# smoothieboard-alt-p4.net
KiCad netlist of a schematic drawn in Altium Designer
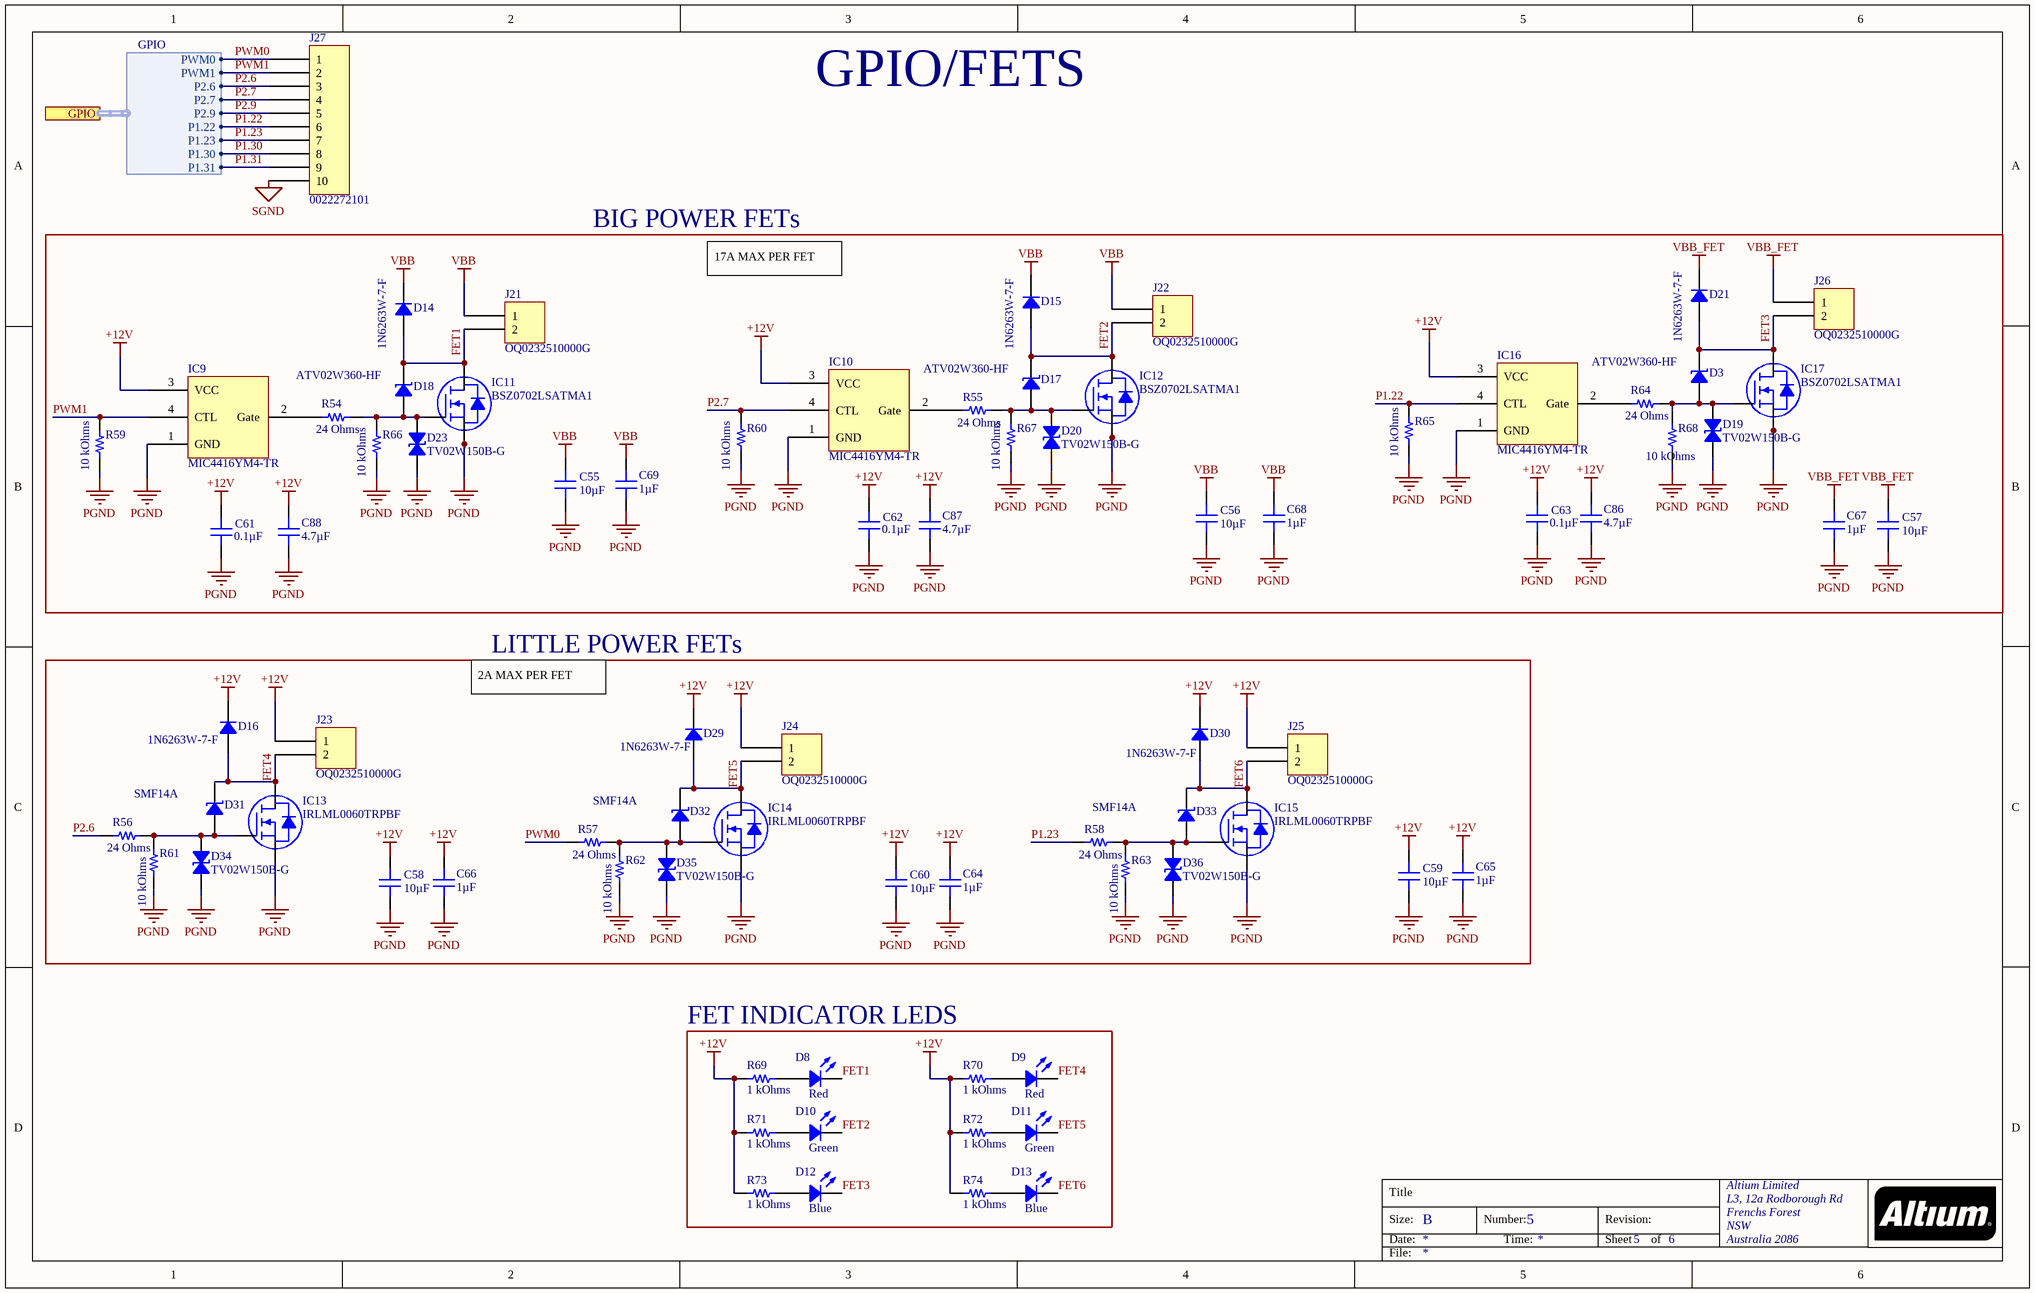
[diagram p0: smoothieboard-alt-p4.SchDoc]

(export (version "E")
  (design (tool "Eeschema 10.0.6"))
  (components
    (comp (ref "C55")
      (value "10µF")
      (footprint "CAP 0603_1608")
      (description "CAP CER 10UF 6.3V X5R 0603")
      (fields
        (field (name "PART NUMBER") "GRM188R60J106KE47D")
        (field (name "MANUFACTURER") "Murata Electronics")
      )
      (libsource (lib "CAL") (part "Capacitor"))
    )
    (comp (ref "C56")
      (value "10µF")
      (footprint "CAP 0603_1608")
      (description "CAP CER 10UF 6.3V X5R 0603")
      (fields
        (field (name "PART NUMBER") "GRM188R60J106KE47D")
        (field (name "MANUFACTURER") "Murata Electronics")
      )
      (libsource (lib "CAL") (part "Capacitor"))
    )
    (comp (ref "C57")
      (value "10µF")
      (footprint "CAP 0603_1608")
      (description "CAP CER 10UF 6.3V X5R 0603")
      (fields
        (field (name "PART NUMBER") "GRM188R60J106KE47D")
        (field (name "MANUFACTURER") "Murata Electronics")
      )
      (libsource (lib "CAL") (part "Capacitor"))
    )
    (comp (ref "C58")
      (value "10µF")
      (footprint "CAP 0603_1608")
      (description "CAP CER 10UF 6.3V X5R 0603")
      (fields
        (field (name "PART NUMBER") "GRM188R60J106KE47D")
        (field (name "MANUFACTURER") "Murata Electronics")
      )
      (libsource (lib "CAL") (part "Capacitor"))
    )
    (comp (ref "C59")
      (value "10µF")
      (footprint "CAP 0603_1608")
      (description "CAP CER 10UF 6.3V X5R 0603")
      (fields
        (field (name "PART NUMBER") "GRM188R60J106KE47D")
        (field (name "MANUFACTURER") "Murata Electronics")
      )
      (libsource (lib "CAL") (part "Capacitor"))
    )
    (comp (ref "C60")
      (value "10µF")
      (footprint "CAP 0603_1608")
      (description "CAP CER 10UF 6.3V X5R 0603")
      (fields
        (field (name "PART NUMBER") "GRM188R60J106KE47D")
        (field (name "MANUFACTURER") "Murata Electronics")
      )
      (libsource (lib "CAL") (part "Capacitor"))
    )
    (comp (ref "C61")
      (value "0.1µF")
      (footprint "CAP 0603_1608")
      (description "CAP CER 0.1UF 50V X7R 0603")
      (fields
        (field (name "PART NUMBER") "CML0603X7R104KT50V")
        (field (name "MANUFACTURER") "Stackpole Electronics Inc")
      )
      (libsource (lib "CAL") (part "Capacitor"))
    )
    (comp (ref "C62")
      (value "0.1µF")
      (footprint "CAP 0603_1608")
      (description "CAP CER 0.1UF 50V X7R 0603")
      (fields
        (field (name "PART NUMBER") "CML0603X7R104KT50V")
        (field (name "MANUFACTURER") "Stackpole Electronics Inc")
      )
      (libsource (lib "CAL") (part "Capacitor"))
    )
    (comp (ref "C63")
      (value "0.1µF")
      (footprint "CAP 0603_1608")
      (description "CAP CER 0.1UF 50V X7R 0603")
      (fields
        (field (name "PART NUMBER") "CML0603X7R104KT50V")
        (field (name "MANUFACTURER") "Stackpole Electronics Inc")
      )
      (libsource (lib "CAL") (part "Capacitor"))
    )
    (comp (ref "C64")
      (value "1µF")
      (footprint "CAP 0805_2012")
      (description "CAP CER 1UF 100V X7R 0805")
      (fields (field (name "PART NUMBER") "08051C105K4Z2A") (field (name "MANUFACTURER") "AVX Corporation"))
      (libsource (lib "CAL") (part "Capacitor"))
    )
    (comp (ref "C65")
      (value "1µF")
      (footprint "CAP 0805_2012")
      (description "CAP CER 1UF 100V X7R 0805")
      (fields (field (name "PART NUMBER") "08051C105K4Z2A") (field (name "MANUFACTURER") "AVX Corporation"))
      (libsource (lib "CAL") (part "Capacitor"))
    )
    (comp (ref "C66")
      (value "1µF")
      (footprint "CAP 0805_2012")
      (description "CAP CER 1UF 100V X7R 0805")
      (fields (field (name "PART NUMBER") "08051C105K4Z2A") (field (name "MANUFACTURER") "AVX Corporation"))
      (libsource (lib "CAL") (part "Capacitor"))
    )
    (comp (ref "C67")
      (value "1µF")
      (footprint "CAP 0805_2012")
      (description "CAP CER 1UF 100V X7R 0805")
      (fields (field (name "PART NUMBER") "08051C105K4Z2A") (field (name "MANUFACTURER") "AVX Corporation"))
      (libsource (lib "CAL") (part "Capacitor"))
    )
    (comp (ref "C68")
      (value "1µF")
      (footprint "CAP 0805_2012")
      (description "CAP CER 1UF 100V X7R 0805")
      (fields (field (name "PART NUMBER") "08051C105K4Z2A") (field (name "MANUFACTURER") "AVX Corporation"))
      (libsource (lib "CAL") (part "Capacitor"))
    )
    (comp (ref "C69")
      (value "1µF")
      (footprint "CAP 0805_2012")
      (description "CAP CER 1UF 100V X7R 0805")
      (fields (field (name "PART NUMBER") "08051C105K4Z2A") (field (name "MANUFACTURER") "AVX Corporation"))
      (libsource (lib "CAL") (part "Capacitor"))
    )
    (comp (ref "C86")
      (value "4.7µF")
      (footprint "CAP 0603_1608")
      (description "CAP CER 4.7UF 16V X5R 0603")
      (fields
        (field (name "PART NUMBER") "C1608X5R1C475K080AE")
        (field (name "MANUFACTURER") "TDK Corporation")
      )
      (libsource (lib "CAL") (part "Capacitor"))
    )
    (comp (ref "C87")
      (value "4.7µF")
      (footprint "CAP 0603_1608")
      (description "CAP CER 4.7UF 16V X5R 0603")
      (fields
        (field (name "PART NUMBER") "C1608X5R1C475K080AE")
        (field (name "MANUFACTURER") "TDK Corporation")
      )
      (libsource (lib "CAL") (part "Capacitor"))
    )
    (comp (ref "C88")
      (value "4.7µF")
      (footprint "CAP 0603_1608")
      (description "CAP CER 4.7UF 16V X5R 0603")
      (fields
        (field (name "PART NUMBER") "C1608X5R1C475K080AE")
        (field (name "MANUFACTURER") "TDK Corporation")
      )
      (libsource (lib "CAL") (part "Capacitor"))
    )
    (comp (ref "D3")
      (value "ATV02W360-HF")
      (footprint "SOD123F")
      (description "TVS DIODE 36V 58.1V SOD123")
      (fields (field (name "MANUFACTURER") "Comchip Technology"))
      (libsource (lib "CAL") (part "DIODE TVS UNI"))
    )
    (comp (ref "D8")
      (value "Red")
      (footprint "LED 0805_2012 RED")
      (description "LED RED CLEAR SMD")
      (fields (field (name "PART NUMBER") "LTST-C171KRKT") (field (name "MANUFACTURER") "Lite-On Inc."))
      (libsource (lib "CAL") (part "LED"))
    )
    (comp (ref "D9")
      (value "Red")
      (footprint "LED 0805_2012 RED")
      (description "LED RED CLEAR SMD")
      (fields (field (name "PART NUMBER") "LTST-C171KRKT") (field (name "MANUFACTURER") "Lite-On Inc."))
      (libsource (lib "CAL") (part "LED"))
    )
    (comp (ref "D10")
      (value "Green")
      (footprint "LED 0805_2012 GREEN")
      (description "LED GREEN CLEAR SMD")
      (fields (field (name "PART NUMBER") "LTST-C171KGKT") (field (name "MANUFACTURER") "Lite-On Inc."))
      (libsource (lib "CAL") (part "LED"))
    )
    (comp (ref "D11")
      (value "Green")
      (footprint "LED 0805_2012 GREEN")
      (description "LED GREEN CLEAR SMD")
      (fields (field (name "PART NUMBER") "LTST-C171KGKT") (field (name "MANUFACTURER") "Lite-On Inc."))
      (libsource (lib "CAL") (part "LED"))
    )
    (comp (ref "D12")
      (value "Blue")
      (footprint "LED 0805_2012 BLUE")
      (description "LED BLUE CLEAR SMD")
      (fields (field (name "PART NUMBER") "LTST-C170TBKT") (field (name "MANUFACTURER") "Lite-On Inc."))
      (libsource (lib "CAL") (part "LED"))
    )
    (comp (ref "D13")
      (value "Blue")
      (footprint "LED 0805_2012 BLUE")
      (description "LED BLUE CLEAR SMD")
      (fields (field (name "PART NUMBER") "LTST-C170TBKT") (field (name "MANUFACTURER") "Lite-On Inc."))
      (libsource (lib "CAL") (part "LED"))
    )
    (comp (ref "D14")
      (value "1N6263W-7-F")
      (footprint "SOD-123")
      (description "DIODE SCHOTTKY 60V 15MA SOD123")
      (fields (field (name "MANUFACTURER") "Diodes Incorporated"))
      (libsource (lib "CAL") (part "Diode"))
    )
    (comp (ref "D15")
      (value "1N6263W-7-F")
      (footprint "SOD-123")
      (description "DIODE SCHOTTKY 60V 15MA SOD123")
      (fields (field (name "MANUFACTURER") "Diodes Incorporated"))
      (libsource (lib "CAL") (part "Diode"))
    )
    (comp (ref "D16")
      (value "1N6263W-7-F")
      (footprint "SOD-123")
      (description "DIODE SCHOTTKY 60V 15MA SOD123")
      (fields (field (name "MANUFACTURER") "Diodes Incorporated"))
      (libsource (lib "CAL") (part "Diode"))
    )
    (comp (ref "D17")
      (value "ATV02W360-HF")
      (footprint "SOD123F")
      (description "TVS DIODE 36V 58.1V SOD123")
      (fields (field (name "MANUFACTURER") "Comchip Technology"))
      (libsource (lib "CAL") (part "DIODE TVS UNI"))
    )
    (comp (ref "D18")
      (value "ATV02W360-HF")
      (footprint "SOD123F")
      (description "TVS DIODE 36V 58.1V SOD123")
      (fields (field (name "MANUFACTURER") "Comchip Technology"))
      (libsource (lib "CAL") (part "DIODE TVS UNI"))
    )
    (comp (ref "D19")
      (value "TV02W150B-G")
      (footprint "SOD-123")
      (description "TVS DIODE 15V 24.4V SOD123")
      (fields (field (name "MANUFACTURER") "Comchip Technology"))
      (libsource (lib "CAL") (part "Diode TVS"))
    )
    (comp (ref "D20")
      (value "TV02W150B-G")
      (footprint "SOD-123")
      (description "TVS DIODE 15V 24.4V SOD123")
      (fields (field (name "MANUFACTURER") "Comchip Technology"))
      (libsource (lib "CAL") (part "Diode TVS"))
    )
    (comp (ref "D21")
      (value "1N6263W-7-F")
      (footprint "SOD-123")
      (description "DIODE SCHOTTKY 60V 15MA SOD123")
      (fields (field (name "MANUFACTURER") "Diodes Incorporated"))
      (libsource (lib "CAL") (part "Diode"))
    )
    (comp (ref "D23")
      (value "TV02W150B-G")
      (footprint "SOD-123")
      (description "TVS DIODE 15V 24.4V SOD123")
      (fields (field (name "MANUFACTURER") "Comchip Technology"))
      (libsource (lib "CAL") (part "Diode TVS"))
    )
    (comp (ref "D29")
      (value "1N6263W-7-F")
      (footprint "SOD-123")
      (description "DIODE SCHOTTKY 60V 15MA SOD123")
      (fields (field (name "MANUFACTURER") "Diodes Incorporated"))
      (libsource (lib "CAL") (part "Diode"))
    )
    (comp (ref "D30")
      (value "1N6263W-7-F")
      (footprint "SOD-123")
      (description "DIODE SCHOTTKY 60V 15MA SOD123")
      (fields (field (name "MANUFACTURER") "Diodes Incorporated"))
      (libsource (lib "CAL") (part "Diode"))
    )
    (comp (ref "D31")
      (value "SMF14A")
      (footprint "SOD123F")
      (description "TVS DIODE 14V 23.2V SOD123F")
      (fields (field (name "MANUFACTURER") "Littelfuse Inc."))
      (libsource (lib "CAL") (part "DIODE TVS UNI"))
    )
    (comp (ref "D32")
      (value "SMF14A")
      (footprint "SOD123F")
      (description "TVS DIODE 14V 23.2V SOD123F")
      (fields (field (name "MANUFACTURER") "Littelfuse Inc."))
      (libsource (lib "CAL") (part "DIODE TVS UNI"))
    )
    (comp (ref "D33")
      (value "SMF14A")
      (footprint "SOD123F")
      (description "TVS DIODE 14V 23.2V SOD123F")
      (fields (field (name "MANUFACTURER") "Littelfuse Inc."))
      (libsource (lib "CAL") (part "DIODE TVS UNI"))
    )
    (comp (ref "D34")
      (value "TV02W150B-G")
      (footprint "SOD-123")
      (description "TVS DIODE 15V 24.4V SOD123")
      (fields (field (name "MANUFACTURER") "Comchip Technology"))
      (libsource (lib "CAL") (part "Diode TVS"))
    )
    (comp (ref "D35")
      (value "TV02W150B-G")
      (footprint "SOD-123")
      (description "TVS DIODE 15V 24.4V SOD123")
      (fields (field (name "MANUFACTURER") "Comchip Technology"))
      (libsource (lib "CAL") (part "Diode TVS"))
    )
    (comp (ref "D36")
      (value "TV02W150B-G")
      (footprint "SOD-123")
      (description "TVS DIODE 15V 24.4V SOD123")
      (fields (field (name "MANUFACTURER") "Comchip Technology"))
      (libsource (lib "CAL") (part "Diode TVS"))
    )
    (comp (ref "IC9")
      (value "MIC4416YM4-TR")
      (footprint "MICROCHIP SOT-143-4")
      (description "IC GATE DRVR LOW-SIDE SOT143")
      (fields (field (name "MANUFACTURER") "Microchip Technology"))
      (libsource (lib "CAL") (part "MICROCHIP MIC4416"))
    )
    (comp (ref "IC10")
      (value "MIC4416YM4-TR")
      (footprint "MICROCHIP SOT-143-4")
      (description "IC GATE DRVR LOW-SIDE SOT143")
      (fields (field (name "MANUFACTURER") "Microchip Technology"))
      (libsource (lib "CAL") (part "MICROCHIP MIC4416"))
    )
    (comp (ref "IC11")
      (value "BSZ0702LSATMA1")
      (footprint "INFINEON PG-TSDSON-8")
      (description "TRENCH 40<-<100V")
      (fields (field (name "MANUFACTURER") "Infineon Technologies"))
      (libsource (lib "CAL") (part "INFINEON BSZ MOSFET N-CH"))
    )
    (comp (ref "IC12")
      (value "BSZ0702LSATMA1")
      (footprint "INFINEON PG-TSDSON-8")
      (description "TRENCH 40<-<100V")
      (fields (field (name "MANUFACTURER") "Infineon Technologies"))
      (libsource (lib "CAL") (part "INFINEON BSZ MOSFET N-CH"))
    )
    (comp (ref "IC13")
      (value "IRLML0060TRPBF")
      (footprint "INFINEON SOT-23-3")
      (description "MOSFET N-CH 60V 2.7A SOT-23-3")
      (fields (field (name "MANUFACTURER") "Infineon Technologies"))
      (libsource (lib "CAL") (part "INFINEON MOSFET N-CH SOT-23-3 GSD"))
    )
    (comp (ref "IC14")
      (value "IRLML0060TRPBF")
      (footprint "INFINEON SOT-23-3")
      (description "MOSFET N-CH 60V 2.7A SOT-23-3")
      (fields (field (name "MANUFACTURER") "Infineon Technologies"))
      (libsource (lib "CAL") (part "INFINEON MOSFET N-CH SOT-23-3 GSD"))
    )
    (comp (ref "IC15")
      (value "IRLML0060TRPBF")
      (footprint "INFINEON SOT-23-3")
      (description "MOSFET N-CH 60V 2.7A SOT-23-3")
      (fields (field (name "MANUFACTURER") "Infineon Technologies"))
      (libsource (lib "CAL") (part "INFINEON MOSFET N-CH SOT-23-3 GSD"))
    )
    (comp (ref "IC16")
      (value "MIC4416YM4-TR")
      (footprint "MICROCHIP SOT-143-4")
      (description "IC GATE DRVR LOW-SIDE SOT143")
      (fields (field (name "MANUFACTURER") "Microchip Technology"))
      (libsource (lib "CAL") (part "MICROCHIP MIC4416"))
    )
    (comp (ref "IC17")
      (value "BSZ0702LSATMA1")
      (footprint "INFINEON PG-TSDSON-8")
      (description "TRENCH 40<-<100V")
      (fields (field (name "MANUFACTURER") "Infineon Technologies"))
      (libsource (lib "CAL") (part "INFINEON BSZ MOSFET N-CH"))
    )
    (comp (ref "J21")
      (value "OQ0232510000G")
      (footprint "FCI 06-381-2PIN")
      (description "TERM BLOCK HDR 2POS 90DEG 3.81MM")
      (fields (field (name "MANUFACTURER") "Amphenol Anytek"))
      (libsource (lib "CAL") (part "2 Pin"))
    )
    (comp (ref "J22")
      (value "OQ0232510000G")
      (footprint "FCI 06-381-2PIN")
      (description "TERM BLOCK HDR 2POS 90DEG 3.81MM")
      (fields (field (name "MANUFACTURER") "Amphenol Anytek"))
      (libsource (lib "CAL") (part "2 Pin"))
    )
    (comp (ref "J23")
      (value "OQ0232510000G")
      (footprint "FCI 06-381-2PIN")
      (description "TERM BLOCK HDR 2POS 90DEG 3.81MM")
      (fields (field (name "MANUFACTURER") "Amphenol Anytek"))
      (libsource (lib "CAL") (part "2 Pin"))
    )
    (comp (ref "J24")
      (value "OQ0232510000G")
      (footprint "FCI 06-381-2PIN")
      (description "TERM BLOCK HDR 2POS 90DEG 3.81MM")
      (fields (field (name "MANUFACTURER") "Amphenol Anytek"))
      (libsource (lib "CAL") (part "2 Pin"))
    )
    (comp (ref "J25")
      (value "OQ0232510000G")
      (footprint "FCI 06-381-2PIN")
      (description "TERM BLOCK HDR 2POS 90DEG 3.81MM")
      (fields (field (name "MANUFACTURER") "Amphenol Anytek"))
      (libsource (lib "CAL") (part "2 Pin"))
    )
    (comp (ref "J26")
      (value "OQ0232510000G")
      (footprint "FCI 06-381-2PIN")
      (description "TERM BLOCK HDR 2POS 90DEG 3.81MM")
      (fields (field (name "MANUFACTURER") "Amphenol Anytek"))
      (libsource (lib "CAL") (part "2 Pin"))
    )
    (comp (ref "J27")
      (value "0022272101")
      (footprint "MOLEX KK 0022272101")
      (description "CONN HEADER VERT 10POS 2.54MM")
      (fields (field (name "MANUFACTURER") "Molex"))
      (libsource (lib "CAL") (part "10 Pin"))
    )
    (comp (ref "R54")
      (value "24 Ohms")
      (footprint "RES 0402_1005")
      (description "RES SMD 24 OHM 1% 1/5W 0402")
      (fields
        (field (name "PART NUMBER") "ERJ-PA2F24R0X")
        (field (name "MANUFACTURER") "Panasonic Electronic Components")
      )
      (libsource (lib "CAL") (part "Resistor"))
    )
    (comp (ref "R55")
      (value "24 Ohms")
      (footprint "RES 0402_1005")
      (description "RES SMD 24 OHM 1% 1/5W 0402")
      (fields
        (field (name "PART NUMBER") "ERJ-PA2F24R0X")
        (field (name "MANUFACTURER") "Panasonic Electronic Components")
      )
      (libsource (lib "CAL") (part "Resistor"))
    )
    (comp (ref "R56")
      (value "24 Ohms")
      (footprint "RES 0402_1005")
      (description "RES SMD 24 OHM 1% 1/5W 0402")
      (fields
        (field (name "PART NUMBER") "ERJ-PA2F24R0X")
        (field (name "MANUFACTURER") "Panasonic Electronic Components")
      )
      (libsource (lib "CAL") (part "Resistor"))
    )
    (comp (ref "R57")
      (value "24 Ohms")
      (footprint "RES 0402_1005")
      (description "RES SMD 24 OHM 1% 1/5W 0402")
      (fields
        (field (name "PART NUMBER") "ERJ-PA2F24R0X")
        (field (name "MANUFACTURER") "Panasonic Electronic Components")
      )
      (libsource (lib "CAL") (part "Resistor"))
    )
    (comp (ref "R58")
      (value "24 Ohms")
      (footprint "RES 0402_1005")
      (description "RES SMD 24 OHM 1% 1/5W 0402")
      (fields
        (field (name "PART NUMBER") "ERJ-PA2F24R0X")
        (field (name "MANUFACTURER") "Panasonic Electronic Components")
      )
      (libsource (lib "CAL") (part "Resistor"))
    )
    (comp (ref "R59")
      (value "10 kOhms")
      (footprint "RES 0402_1005")
      (description "RES SMD 10K OHM 5% 1/16W 0402")
      (fields (field (name "PART NUMBER") "CRCW040210K0JNTD") (field (name "MANUFACTURER") "Vishay Dale"))
      (libsource (lib "CAL") (part "Resistor"))
    )
    (comp (ref "R60")
      (value "10 kOhms")
      (footprint "RES 0402_1005")
      (description "RES SMD 10K OHM 5% 1/16W 0402")
      (fields (field (name "PART NUMBER") "CRCW040210K0JNTD") (field (name "MANUFACTURER") "Vishay Dale"))
      (libsource (lib "CAL") (part "Resistor"))
    )
    (comp (ref "R61")
      (value "10 kOhms")
      (footprint "RES 0402_1005")
      (description "RES SMD 10K OHM 5% 1/16W 0402")
      (fields (field (name "PART NUMBER") "CRCW040210K0JNTD") (field (name "MANUFACTURER") "Vishay Dale"))
      (libsource (lib "CAL") (part "Resistor"))
    )
    (comp (ref "R62")
      (value "10 kOhms")
      (footprint "RES 0402_1005")
      (description "RES SMD 10K OHM 5% 1/16W 0402")
      (fields (field (name "PART NUMBER") "CRCW040210K0JNTD") (field (name "MANUFACTURER") "Vishay Dale"))
      (libsource (lib "CAL") (part "Resistor"))
    )
    (comp (ref "R63")
      (value "10 kOhms")
      (footprint "RES 0402_1005")
      (description "RES SMD 10K OHM 5% 1/16W 0402")
      (fields (field (name "PART NUMBER") "CRCW040210K0JNTD") (field (name "MANUFACTURER") "Vishay Dale"))
      (libsource (lib "CAL") (part "Resistor"))
    )
    (comp (ref "R64")
      (value "24 Ohms")
      (footprint "RES 0402_1005")
      (description "RES SMD 24 OHM 1% 1/5W 0402")
      (fields
        (field (name "PART NUMBER") "ERJ-PA2F24R0X")
        (field (name "MANUFACTURER") "Panasonic Electronic Components")
      )
      (libsource (lib "CAL") (part "Resistor"))
    )
    (comp (ref "R65")
      (value "10 kOhms")
      (footprint "RES 0402_1005")
      (description "RES SMD 10K OHM 5% 1/16W 0402")
      (fields (field (name "PART NUMBER") "CRCW040210K0JNTD") (field (name "MANUFACTURER") "Vishay Dale"))
      (libsource (lib "CAL") (part "Resistor"))
    )
    (comp (ref "R66")
      (value "10 kOhms")
      (footprint "RES 0402_1005")
      (description "RES SMD 10K OHM 5% 1/16W 0402")
      (fields (field (name "PART NUMBER") "CRCW040210K0JNTD") (field (name "MANUFACTURER") "Vishay Dale"))
      (libsource (lib "CAL") (part "Resistor"))
    )
    (comp (ref "R67")
      (value "10 kOhms")
      (footprint "RES 0402_1005")
      (description "RES SMD 10K OHM 5% 1/16W 0402")
      (fields (field (name "PART NUMBER") "CRCW040210K0JNTD") (field (name "MANUFACTURER") "Vishay Dale"))
      (libsource (lib "CAL") (part "Resistor"))
    )
    (comp (ref "R68")
      (value "10 kOhms")
      (footprint "RES 0402_1005")
      (description "RES SMD 10K OHM 5% 1/16W 0402")
      (fields (field (name "PART NUMBER") "CRCW040210K0JNTD") (field (name "MANUFACTURER") "Vishay Dale"))
      (libsource (lib "CAL") (part "Resistor"))
    )
    (comp (ref "R69")
      (value "1 kOhms")
      (footprint "RES 0402_1005")
      (description "RES SMD 1K OHM 1% 1/5W 0402")
      (fields (field (name "PART NUMBER") "CRCW04021K00FKEDHP") (field (name "MANUFACTURER") "Vishay Dale"))
      (libsource (lib "CAL") (part "Resistor"))
    )
    (comp (ref "R70")
      (value "1 kOhms")
      (footprint "RES 0402_1005")
      (description "RES SMD 1K OHM 1% 1/5W 0402")
      (fields (field (name "PART NUMBER") "CRCW04021K00FKEDHP") (field (name "MANUFACTURER") "Vishay Dale"))
      (libsource (lib "CAL") (part "Resistor"))
    )
    (comp (ref "R71")
      (value "1 kOhms")
      (footprint "RES 0402_1005")
      (description "RES SMD 1K OHM 1% 1/5W 0402")
      (fields (field (name "PART NUMBER") "CRCW04021K00FKEDHP") (field (name "MANUFACTURER") "Vishay Dale"))
      (libsource (lib "CAL") (part "Resistor"))
    )
    (comp (ref "R72")
      (value "1 kOhms")
      (footprint "RES 0402_1005")
      (description "RES SMD 1K OHM 1% 1/5W 0402")
      (fields (field (name "PART NUMBER") "CRCW04021K00FKEDHP") (field (name "MANUFACTURER") "Vishay Dale"))
      (libsource (lib "CAL") (part "Resistor"))
    )
    (comp (ref "R73")
      (value "1 kOhms")
      (footprint "RES 0402_1005")
      (description "RES SMD 1K OHM 1% 1/5W 0402")
      (fields (field (name "PART NUMBER") "CRCW04021K00FKEDHP") (field (name "MANUFACTURER") "Vishay Dale"))
      (libsource (lib "CAL") (part "Resistor"))
    )
    (comp (ref "R74")
      (value "1 kOhms")
      (footprint "RES 0402_1005")
      (description "RES SMD 1K OHM 1% 1/5W 0402")
      (fields (field (name "PART NUMBER") "CRCW04021K00FKEDHP") (field (name "MANUFACTURER") "Vishay Dale"))
      (libsource (lib "CAL") (part "Resistor"))
    )
  )
  (nets
    (net (code "2") (name "+12V") (class "Default")
      (node (ref "C58") (pin "2") (pinfunction "2_2") (pintype "passive"))
      (node (ref "C59") (pin "2") (pinfunction "2_2") (pintype "passive"))
      (node (ref "C60") (pin "2") (pinfunction "2_2") (pintype "passive"))
      (node (ref "C61") (pin "2") (pinfunction "2_2") (pintype "passive"))
      (node (ref "C62") (pin "2") (pinfunction "2_2") (pintype "passive"))
      (node (ref "C63") (pin "2") (pinfunction "2_2") (pintype "passive"))
      (node (ref "C64") (pin "2") (pinfunction "2_2") (pintype "passive"))
      (node (ref "C65") (pin "2") (pinfunction "2_2") (pintype "passive"))
      (node (ref "C66") (pin "2") (pinfunction "2_2") (pintype "passive"))
      (node (ref "C86") (pin "2") (pinfunction "2_2") (pintype "passive"))
      (node (ref "C87") (pin "2") (pinfunction "2_2") (pintype "passive"))
      (node (ref "C88") (pin "2") (pinfunction "2_2") (pintype "passive"))
      (node (ref "D16") (pin "2") (pinfunction "2_2") (pintype "passive"))
      (node (ref "D29") (pin "2") (pinfunction "2_2") (pintype "passive"))
      (node (ref "D30") (pin "2") (pinfunction "2_2") (pintype "passive"))
      (node (ref "IC10") (pin "3") (pinfunction "VCC_3") (pintype "passive"))
      (node (ref "IC16") (pin "3") (pinfunction "VCC_3") (pintype "passive"))
      (node (ref "IC9") (pin "3") (pinfunction "VCC_3") (pintype "passive"))
      (node (ref "J23") (pin "1") (pinfunction "1_1") (pintype "passive"))
      (node (ref "J24") (pin "1") (pinfunction "1_1") (pintype "passive"))
      (node (ref "J25") (pin "1") (pinfunction "1_1") (pintype "passive"))
      (node (ref "R69") (pin "1") (pinfunction "1_1") (pintype "passive"))
      (node (ref "R70") (pin "1") (pinfunction "1_1") (pintype "passive"))
      (node (ref "R71") (pin "1") (pinfunction "1_1") (pintype "passive"))
      (node (ref "R72") (pin "1") (pinfunction "1_1") (pintype "passive"))
      (node (ref "R73") (pin "1") (pinfunction "1_1") (pintype "passive"))
      (node (ref "R74") (pin "1") (pinfunction "1_1") (pintype "passive"))
    )
    (net (code "3") (name "/FET1") (class "Default")
      (node (ref "D14") (pin "1") (pinfunction "1_1") (pintype "passive"))
      (node (ref "D18") (pin "2") (pinfunction "2_2") (pintype "passive"))
      (node (ref "D8") (pin "2") (pinfunction "2_2") (pintype "passive"))
      (node (ref "IC11") (pin "5") (pinfunction "D_5") (pintype "passive"))
      (node (ref "IC11") (pin "6") (pinfunction "D_6") (pintype "passive"))
      (node (ref "IC11") (pin "7") (pinfunction "D_7") (pintype "passive"))
      (node (ref "IC11") (pin "8") (pinfunction "D_8") (pintype "passive"))
      (node (ref "J21") (pin "2") (pinfunction "2_2") (pintype "passive"))
    )
    (net (code "4") (name "/FET2") (class "Default")
      (node (ref "D10") (pin "2") (pinfunction "2_2") (pintype "passive"))
      (node (ref "D15") (pin "1") (pinfunction "1_1") (pintype "passive"))
      (node (ref "D17") (pin "2") (pinfunction "2_2") (pintype "passive"))
      (node (ref "IC12") (pin "5") (pinfunction "D_5") (pintype "passive"))
      (node (ref "IC12") (pin "6") (pinfunction "D_6") (pintype "passive"))
      (node (ref "IC12") (pin "7") (pinfunction "D_7") (pintype "passive"))
      (node (ref "IC12") (pin "8") (pinfunction "D_8") (pintype "passive"))
      (node (ref "J22") (pin "2") (pinfunction "2_2") (pintype "passive"))
    )
    (net (code "5") (name "/FET3") (class "Default")
      (node (ref "D12") (pin "2") (pinfunction "2_2") (pintype "passive"))
      (node (ref "D21") (pin "1") (pinfunction "1_1") (pintype "passive"))
      (node (ref "D3") (pin "2") (pinfunction "2_2") (pintype "passive"))
      (node (ref "IC17") (pin "5") (pinfunction "D_5") (pintype "passive"))
      (node (ref "IC17") (pin "6") (pinfunction "D_6") (pintype "passive"))
      (node (ref "IC17") (pin "7") (pinfunction "D_7") (pintype "passive"))
      (node (ref "IC17") (pin "8") (pinfunction "D_8") (pintype "passive"))
      (node (ref "J26") (pin "2") (pinfunction "2_2") (pintype "passive"))
    )
    (net (code "6") (name "/FET4") (class "Default")
      (node (ref "D16") (pin "1") (pinfunction "1_1") (pintype "passive"))
      (node (ref "D31") (pin "2") (pinfunction "2_2") (pintype "passive"))
      (node (ref "D9") (pin "2") (pinfunction "2_2") (pintype "passive"))
      (node (ref "IC13") (pin "3") (pinfunction "D_3") (pintype "passive"))
      (node (ref "J23") (pin "2") (pinfunction "2_2") (pintype "passive"))
    )
    (net (code "7") (name "/FET5") (class "Default")
      (node (ref "D11") (pin "2") (pinfunction "2_2") (pintype "passive"))
      (node (ref "D29") (pin "1") (pinfunction "1_1") (pintype "passive"))
      (node (ref "D32") (pin "2") (pinfunction "2_2") (pintype "passive"))
      (node (ref "IC14") (pin "3") (pinfunction "D_3") (pintype "passive"))
      (node (ref "J24") (pin "2") (pinfunction "2_2") (pintype "passive"))
    )
    (net (code "8") (name "/FET6") (class "Default")
      (node (ref "D13") (pin "2") (pinfunction "2_2") (pintype "passive"))
      (node (ref "D30") (pin "1") (pinfunction "1_1") (pintype "passive"))
      (node (ref "D33") (pin "2") (pinfunction "2_2") (pintype "passive"))
      (node (ref "IC15") (pin "3") (pinfunction "D_3") (pintype "passive"))
      (node (ref "J25") (pin "2") (pinfunction "2_2") (pintype "passive"))
    )
    (net (code "9") (name "/P1.22") (class "Default")
      (node (ref "IC16") (pin "4") (pinfunction "CTL_4") (pintype "passive"))
      (node (ref "J27") (pin "6") (pinfunction "6_6") (pintype "passive"))
      (node (ref "R65") (pin "2") (pinfunction "2_2") (pintype "passive"))
    )
    (net (code "10") (name "/P1.23") (class "Default")
      (node (ref "J27") (pin "7") (pinfunction "7_7") (pintype "passive"))
      (node (ref "R58") (pin "1") (pinfunction "1_1") (pintype "passive"))
    )
    (net (code "11") (name "/P1.30") (class "Default")
      (node (ref "J27") (pin "8") (pinfunction "8_8") (pintype "passive"))
    )
    (net (code "12") (name "/P1.31") (class "Default")
      (node (ref "J27") (pin "9") (pinfunction "9_9") (pintype "passive"))
    )
    (net (code "13") (name "/P2.6") (class "Default")
      (node (ref "J27") (pin "3") (pinfunction "3_3") (pintype "passive"))
      (node (ref "R56") (pin "1") (pinfunction "1_1") (pintype "passive"))
    )
    (net (code "14") (name "/P2.7") (class "Default")
      (node (ref "IC10") (pin "4") (pinfunction "CTL_4") (pintype "passive"))
      (node (ref "J27") (pin "4") (pinfunction "4_4") (pintype "passive"))
      (node (ref "R60") (pin "2") (pinfunction "2_2") (pintype "passive"))
    )
    (net (code "15") (name "/P2.9") (class "Default")
      (node (ref "J27") (pin "5") (pinfunction "5_5") (pintype "passive"))
    )
    (net (code "16") (name "/PWM0") (class "Default")
      (node (ref "J27") (pin "1") (pinfunction "1_1") (pintype "passive"))
      (node (ref "R57") (pin "1") (pinfunction "1_1") (pintype "passive"))
    )
    (net (code "17") (name "/PWM1") (class "Default")
      (node (ref "IC9") (pin "4") (pinfunction "CTL_4") (pintype "passive"))
      (node (ref "J27") (pin "2") (pinfunction "2_2") (pintype "passive"))
      (node (ref "R59") (pin "2") (pinfunction "2_2") (pintype "passive"))
    )
    (net (code "19") (name "Net-(D8-Pad1)") (class "Default")
      (node (ref "D8") (pin "1") (pinfunction "1_1") (pintype "passive"))
      (node (ref "R69") (pin "2") (pinfunction "2_2") (pintype "passive"))
    )
    (net (code "20") (name "Net-(D9-Pad1)") (class "Default")
      (node (ref "D9") (pin "1") (pinfunction "1_1") (pintype "passive"))
      (node (ref "R70") (pin "2") (pinfunction "2_2") (pintype "passive"))
    )
    (net (code "21") (name "Net-(D10-Pad1)") (class "Default")
      (node (ref "D10") (pin "1") (pinfunction "1_1") (pintype "passive"))
      (node (ref "R71") (pin "2") (pinfunction "2_2") (pintype "passive"))
    )
    (net (code "22") (name "Net-(D11-Pad1)") (class "Default")
      (node (ref "D11") (pin "1") (pinfunction "1_1") (pintype "passive"))
      (node (ref "R72") (pin "2") (pinfunction "2_2") (pintype "passive"))
    )
    (net (code "23") (name "Net-(D12-Pad1)") (class "Default")
      (node (ref "D12") (pin "1") (pinfunction "1_1") (pintype "passive"))
      (node (ref "R73") (pin "2") (pinfunction "2_2") (pintype "passive"))
    )
    (net (code "24") (name "Net-(D13-Pad1)") (class "Default")
      (node (ref "D13") (pin "1") (pinfunction "1_1") (pintype "passive"))
      (node (ref "R74") (pin "2") (pinfunction "2_2") (pintype "passive"))
    )
    (net (code "25") (name "Net-(IC9-Gate)") (class "Default")
      (node (ref "IC9") (pin "2") (pinfunction "Gate_2") (pintype "passive"))
      (node (ref "R54") (pin "1") (pinfunction "1_1") (pintype "passive"))
    )
    (net (code "26") (name "Net-(IC10-Gate)") (class "Default")
      (node (ref "IC10") (pin "2") (pinfunction "Gate_2") (pintype "passive"))
      (node (ref "R55") (pin "1") (pinfunction "1_1") (pintype "passive"))
    )
    (net (code "27") (name "Net-(IC11-G)") (class "Default")
      (node (ref "D18") (pin "1") (pinfunction "1_1") (pintype "passive"))
      (node (ref "D23") (pin "2") (pinfunction "2_2") (pintype "passive"))
      (node (ref "IC11") (pin "4") (pinfunction "G_4") (pintype "passive"))
      (node (ref "R54") (pin "2") (pinfunction "2_2") (pintype "passive"))
      (node (ref "R66") (pin "2") (pinfunction "2_2") (pintype "passive"))
    )
    (net (code "28") (name "Net-(IC12-G)") (class "Default")
      (node (ref "D17") (pin "1") (pinfunction "1_1") (pintype "passive"))
      (node (ref "D20") (pin "2") (pinfunction "2_2") (pintype "passive"))
      (node (ref "IC12") (pin "4") (pinfunction "G_4") (pintype "passive"))
      (node (ref "R55") (pin "2") (pinfunction "2_2") (pintype "passive"))
      (node (ref "R67") (pin "2") (pinfunction "2_2") (pintype "passive"))
    )
    (net (code "29") (name "Net-(IC13-G)") (class "Default")
      (node (ref "D31") (pin "1") (pinfunction "1_1") (pintype "passive"))
      (node (ref "D34") (pin "2") (pinfunction "2_2") (pintype "passive"))
      (node (ref "IC13") (pin "1") (pinfunction "G_1") (pintype "passive"))
      (node (ref "R56") (pin "2") (pinfunction "2_2") (pintype "passive"))
      (node (ref "R61") (pin "2") (pinfunction "2_2") (pintype "passive"))
    )
    (net (code "30") (name "Net-(IC14-G)") (class "Default")
      (node (ref "D32") (pin "1") (pinfunction "1_1") (pintype "passive"))
      (node (ref "D35") (pin "2") (pinfunction "2_2") (pintype "passive"))
      (node (ref "IC14") (pin "1") (pinfunction "G_1") (pintype "passive"))
      (node (ref "R57") (pin "2") (pinfunction "2_2") (pintype "passive"))
      (node (ref "R62") (pin "2") (pinfunction "2_2") (pintype "passive"))
    )
    (net (code "31") (name "Net-(IC15-G)") (class "Default")
      (node (ref "D33") (pin "1") (pinfunction "1_1") (pintype "passive"))
      (node (ref "D36") (pin "2") (pinfunction "2_2") (pintype "passive"))
      (node (ref "IC15") (pin "1") (pinfunction "G_1") (pintype "passive"))
      (node (ref "R58") (pin "2") (pinfunction "2_2") (pintype "passive"))
      (node (ref "R63") (pin "2") (pinfunction "2_2") (pintype "passive"))
    )
    (net (code "32") (name "Net-(IC16-Gate)") (class "Default")
      (node (ref "IC16") (pin "2") (pinfunction "Gate_2") (pintype "passive"))
      (node (ref "R64") (pin "1") (pinfunction "1_1") (pintype "passive"))
    )
    (net (code "33") (name "Net-(IC17-G)") (class "Default")
      (node (ref "D19") (pin "2") (pinfunction "2_2") (pintype "passive"))
      (node (ref "D3") (pin "1") (pinfunction "1_1") (pintype "passive"))
      (node (ref "IC17") (pin "4") (pinfunction "G_4") (pintype "passive"))
      (node (ref "R64") (pin "2") (pinfunction "2_2") (pintype "passive"))
      (node (ref "R68") (pin "2") (pinfunction "2_2") (pintype "passive"))
    )
    (net (code "34") (name "PGND") (class "Default")
      (node (ref "C55") (pin "1") (pinfunction "1_1") (pintype "passive"))
      (node (ref "C56") (pin "1") (pinfunction "1_1") (pintype "passive"))
      (node (ref "C57") (pin "1") (pinfunction "1_1") (pintype "passive"))
      (node (ref "C58") (pin "1") (pinfunction "1_1") (pintype "passive"))
      (node (ref "C59") (pin "1") (pinfunction "1_1") (pintype "passive"))
      (node (ref "C60") (pin "1") (pinfunction "1_1") (pintype "passive"))
      (node (ref "C61") (pin "1") (pinfunction "1_1") (pintype "passive"))
      (node (ref "C62") (pin "1") (pinfunction "1_1") (pintype "passive"))
      (node (ref "C63") (pin "1") (pinfunction "1_1") (pintype "passive"))
      (node (ref "C64") (pin "1") (pinfunction "1_1") (pintype "passive"))
      (node (ref "C65") (pin "1") (pinfunction "1_1") (pintype "passive"))
      (node (ref "C66") (pin "1") (pinfunction "1_1") (pintype "passive"))
      (node (ref "C67") (pin "1") (pinfunction "1_1") (pintype "passive"))
      (node (ref "C68") (pin "1") (pinfunction "1_1") (pintype "passive"))
      (node (ref "C69") (pin "1") (pinfunction "1_1") (pintype "passive"))
      (node (ref "C86") (pin "1") (pinfunction "1_1") (pintype "passive"))
      (node (ref "C87") (pin "1") (pinfunction "1_1") (pintype "passive"))
      (node (ref "C88") (pin "1") (pinfunction "1_1") (pintype "passive"))
      (node (ref "D19") (pin "1") (pinfunction "1_1") (pintype "passive"))
      (node (ref "D20") (pin "1") (pinfunction "1_1") (pintype "passive"))
      (node (ref "D23") (pin "1") (pinfunction "1_1") (pintype "passive"))
      (node (ref "D34") (pin "1") (pinfunction "1_1") (pintype "passive"))
      (node (ref "D35") (pin "1") (pinfunction "1_1") (pintype "passive"))
      (node (ref "D36") (pin "1") (pinfunction "1_1") (pintype "passive"))
      (node (ref "IC10") (pin "1") (pinfunction "GND_1") (pintype "passive"))
      (node (ref "IC11") (pin "1") (pinfunction "S_1") (pintype "passive"))
      (node (ref "IC11") (pin "2") (pinfunction "S_2") (pintype "passive"))
      (node (ref "IC11") (pin "3") (pinfunction "S_3") (pintype "passive"))
      (node (ref "IC12") (pin "1") (pinfunction "S_1") (pintype "passive"))
      (node (ref "IC12") (pin "2") (pinfunction "S_2") (pintype "passive"))
      (node (ref "IC12") (pin "3") (pinfunction "S_3") (pintype "passive"))
      (node (ref "IC13") (pin "2") (pinfunction "S_2") (pintype "passive"))
      (node (ref "IC14") (pin "2") (pinfunction "S_2") (pintype "passive"))
      (node (ref "IC15") (pin "2") (pinfunction "S_2") (pintype "passive"))
      (node (ref "IC16") (pin "1") (pinfunction "GND_1") (pintype "passive"))
      (node (ref "IC17") (pin "1") (pinfunction "S_1") (pintype "passive"))
      (node (ref "IC17") (pin "2") (pinfunction "S_2") (pintype "passive"))
      (node (ref "IC17") (pin "3") (pinfunction "S_3") (pintype "passive"))
      (node (ref "IC9") (pin "1") (pinfunction "GND_1") (pintype "passive"))
      (node (ref "R59") (pin "1") (pinfunction "1_1") (pintype "passive"))
      (node (ref "R60") (pin "1") (pinfunction "1_1") (pintype "passive"))
      (node (ref "R61") (pin "1") (pinfunction "1_1") (pintype "passive"))
      (node (ref "R62") (pin "1") (pinfunction "1_1") (pintype "passive"))
      (node (ref "R63") (pin "1") (pinfunction "1_1") (pintype "passive"))
      (node (ref "R65") (pin "1") (pinfunction "1_1") (pintype "passive"))
      (node (ref "R66") (pin "1") (pinfunction "1_1") (pintype "passive"))
      (node (ref "R67") (pin "1") (pinfunction "1_1") (pintype "passive"))
      (node (ref "R68") (pin "1") (pinfunction "1_1") (pintype "passive"))
    )
    (net (code "35") (name "SGND") (class "Default")
      (node (ref "J27") (pin "10") (pinfunction "10_10") (pintype "passive"))
    )
    (net (code "36") (name "VBB") (class "Default")
      (node (ref "C55") (pin "2") (pinfunction "2_2") (pintype "passive"))
      (node (ref "C56") (pin "2") (pinfunction "2_2") (pintype "passive"))
      (node (ref "C68") (pin "2") (pinfunction "2_2") (pintype "passive"))
      (node (ref "C69") (pin "2") (pinfunction "2_2") (pintype "passive"))
      (node (ref "D14") (pin "2") (pinfunction "2_2") (pintype "passive"))
      (node (ref "D15") (pin "2") (pinfunction "2_2") (pintype "passive"))
      (node (ref "J21") (pin "1") (pinfunction "1_1") (pintype "passive"))
      (node (ref "J22") (pin "1") (pinfunction "1_1") (pintype "passive"))
    )
    (net (code "37") (name "VBB_FET") (class "Default")
      (node (ref "C57") (pin "2") (pinfunction "2_2") (pintype "passive"))
      (node (ref "C67") (pin "2") (pinfunction "2_2") (pintype "passive"))
      (node (ref "D21") (pin "2") (pinfunction "2_2") (pintype "passive"))
      (node (ref "J26") (pin "1") (pinfunction "1_1") (pintype "passive"))
    )
  )
)
